# USBiso.net
KiCad netlist of a schematic drawn in Altium Designer
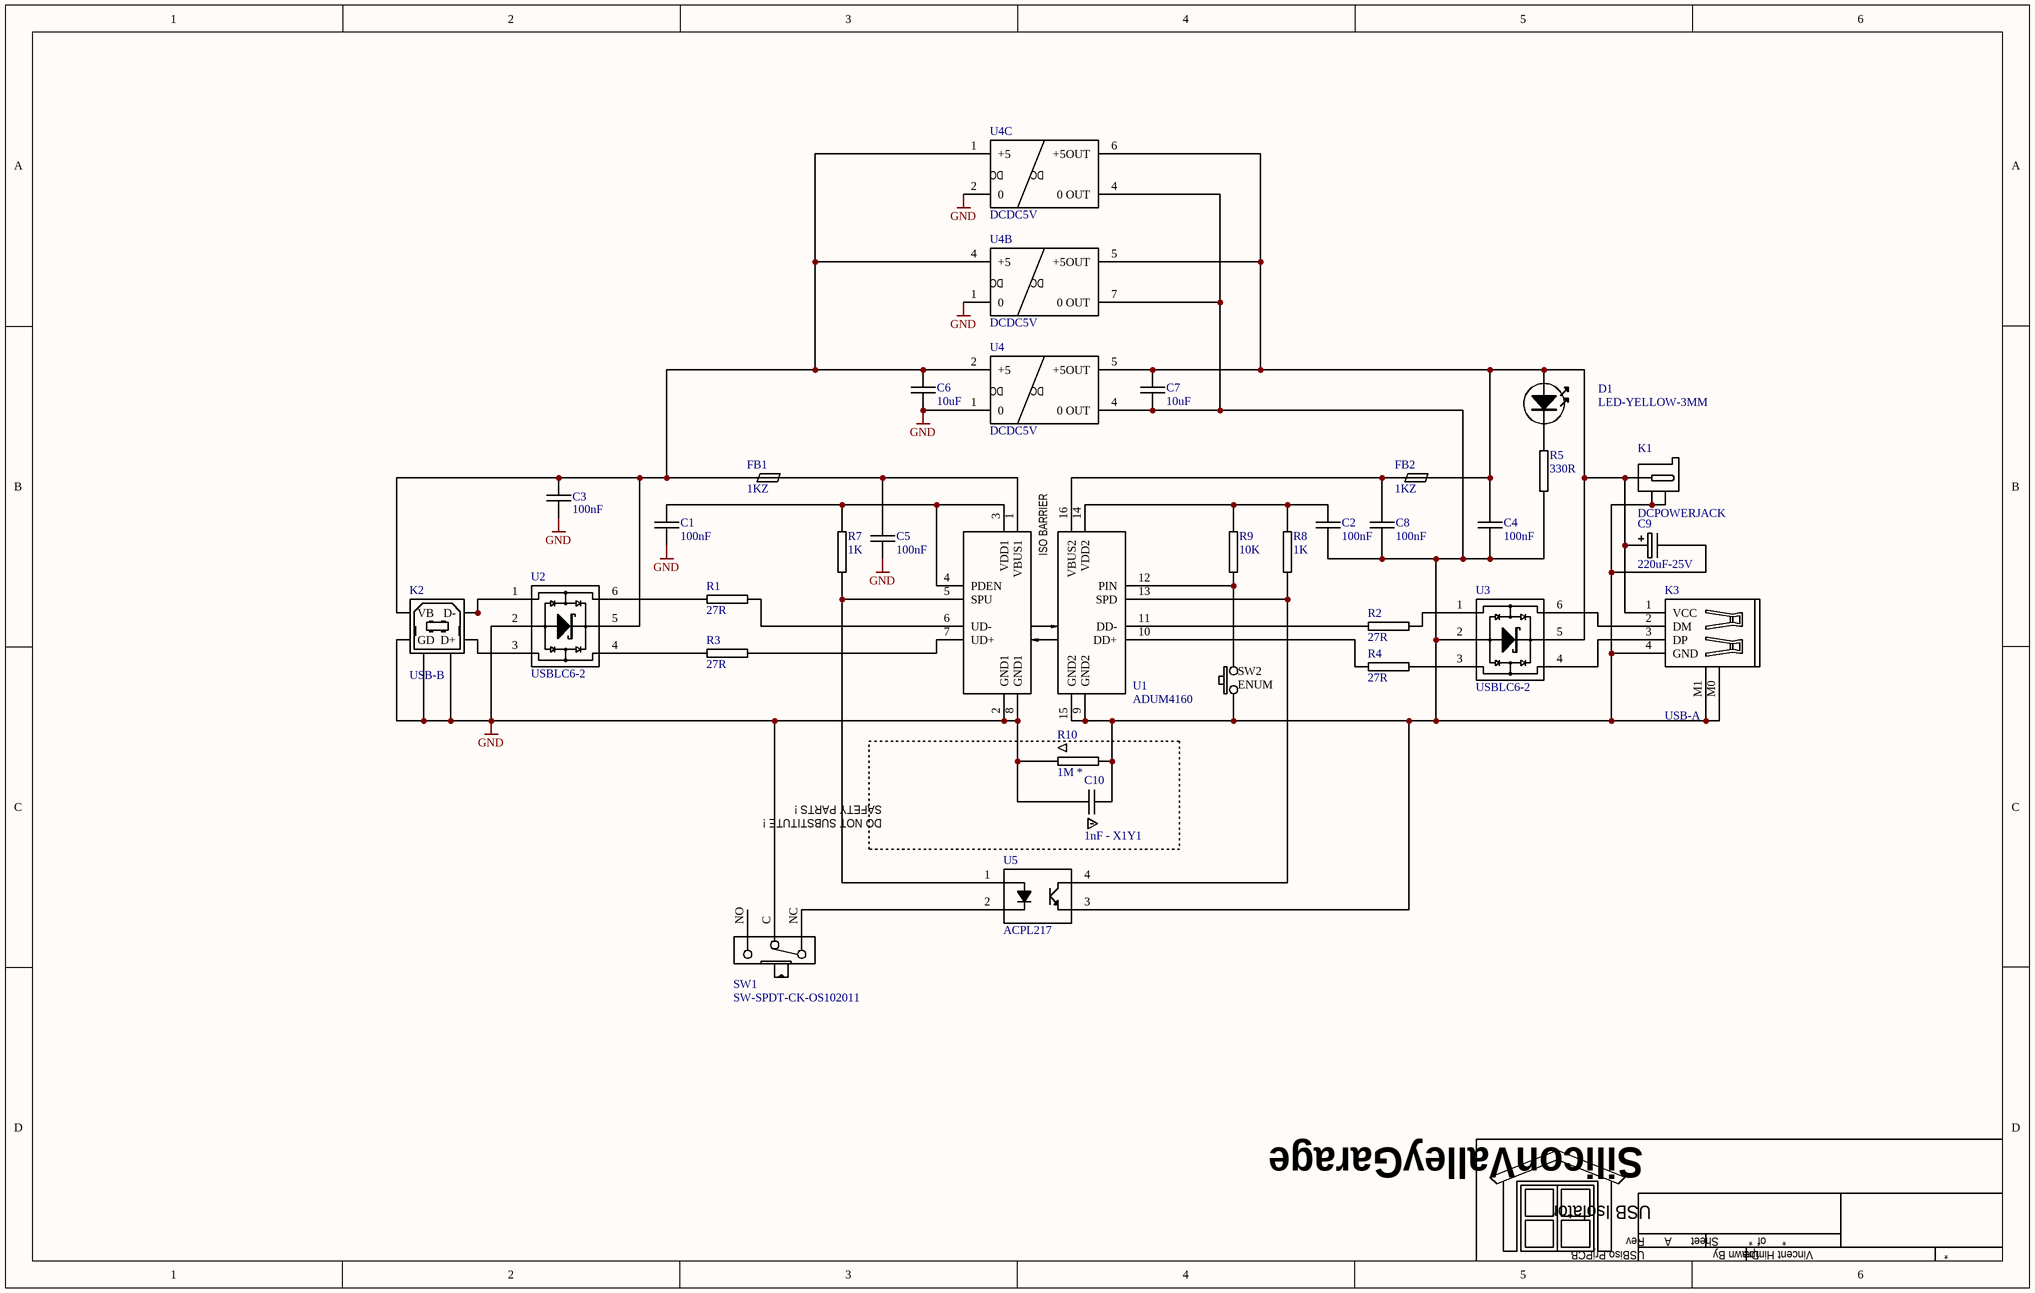
[diagram p0: USBiso.SchDoc]

(export (version "E")
  (design (tool "Eeschema 10.0.6"))
  (components
    (comp (ref "C1")
      (value "100nF")
      (footprint "0805C-TBD")
      (description "CAPACITOR 0805 CERAMIC")
      (libsource (lib "vh_Altium Library") (part "0805C-100nF-25V-X7R-MUR"))
    )
    (comp (ref "C2")
      (value "100nF")
      (footprint "0805C-TBD")
      (description "CAPACITOR 0805 CERAMIC")
      (libsource (lib "vh_Altium Library") (part "0805C-100nF-25V-X7R-MUR"))
    )
    (comp (ref "C3")
      (value "100nF")
      (footprint "0805C-TBD")
      (description "CAPACITOR 0805 CERAMIC")
      (libsource (lib "vh_Altium Library") (part "0805C-100nF-25V-X7R-MUR"))
    )
    (comp (ref "C4")
      (value "100nF")
      (footprint "0805C-TBD")
      (description "CAPACITOR 0805 CERAMIC")
      (libsource (lib "vh_Altium Library") (part "0805C-100nF-25V-X7R-MUR"))
    )
    (comp (ref "C5")
      (value "100nF")
      (footprint "0805C-TBD")
      (description "CAPACITOR 0805 CERAMIC")
      (libsource (lib "vh_Altium Library") (part "0805C-100nF-25V-X7R-MUR"))
    )
    (comp (ref "C6")
      (value "10uF")
      (footprint "0805C-GENERIC")
      (description "CAPACITOR 0805 CERAMIC")
      (fields (field (name "TOLERANCE") "±10%") (field (name "MANUFACTURER") "TDK Corporation"))
      (libsource (lib "vh_Altium Library") (part "0805C-4U7-25V-X5R-TDK"))
    )
    (comp (ref "C7")
      (value "10uF")
      (footprint "0805C-GENERIC")
      (description "CAPACITOR 0805 CERAMIC")
      (fields (field (name "TOLERANCE") "±10%") (field (name "MANUFACTURER") "TDK Corporation"))
      (libsource (lib "vh_Altium Library") (part "0805C-4U7-25V-X5R-TDK"))
    )
    (comp (ref "C8")
      (value "100nF")
      (footprint "0805C-TBD")
      (description "CAPACITOR 0805 CERAMIC")
      (libsource (lib "vh_Altium Library") (part "0805C-100nF-25V-X7R-MUR"))
    )
    (comp (ref "C9")
      (value "220uF-25V")
      (footprint "PANACAP-F-GENERIC")
      (description "GENERIC CAPACITOR POLARISED")
      (libsource (lib "SMD Capacitors Electrolytic") (part "PANACAP-220UF-25V-FK"))
    )
    (comp (ref "C10")
      (value "1nF - X1Y1")
      (footprint "C-X1Y1-10MM")
      (description "CAPACITOR X1Y1 CLASS")
      (libsource (lib "TH Capacitors") (part "C-X1Y1-10MM-1NF"))
    )
    (comp (ref "D1")
      (value "LED-YELLOW-3MM")
      (footprint "LED-3MM-YELLOW")
      (libsource (lib "vh_Altium Library") (part "LED-YELLOW-3MM"))
    )
    (comp (ref "FB1")
      (value "1KZ")
      (footprint "0805FB-1KZ")
      (description "FERRITE BEAD 1000 OHM 6A")
      (libsource (lib "SMD Magnetics") (part "0805FB-1KZ"))
    )
    (comp (ref "FB2")
      (value "1KZ")
      (footprint "0805FB-1KZ")
      (description "FERRITE BEAD 1000 OHM 6A")
      (libsource (lib "SMD Magnetics") (part "0805FB-1KZ"))
    )
    (comp (ref "K1")
      (value "DCPOWERJACK")
      (footprint "DCPOWER")
      (description "CONNN POWERJACK MINI.08\" RA PCMT")
      (fields (field (name "MANUFACTURER PART NUMBER") "RAPC722"))
      (libsource (lib "TH Connectors") (part "DCPOWERJACK"))
    )
    (comp (ref "K2")
      (value "USB-B")
      (footprint "USB-B")
      (description "USB B DEVICE CONNECTOR")
      (libsource (lib "vh_Altium Library") (part "USB-B"))
    )
    (comp (ref "K3")
      (value "USB-A")
      (footprint "usb-a")
      (description "USB A HOST CONNECTOR")
      (libsource (lib "TH Connectors") (part "USB-A"))
    )
    (comp (ref "R1")
      (value "27R")
      (footprint "0805R-27")
      (description "RESISTOR 0805 1/4 WATT THIN FILM")
      (libsource (lib "vh_Altium Library") (part "0805R-27"))
    )
    (comp (ref "R2")
      (value "27R")
      (footprint "0805R-27")
      (description "RESISTOR 0805 1/4 WATT THIN FILM")
      (libsource (lib "vh_Altium Library") (part "0805R-27"))
    )
    (comp (ref "R3")
      (value "27R")
      (footprint "0805R-27")
      (description "RESISTOR 0805 1/4 WATT THIN FILM")
      (libsource (lib "vh_Altium Library") (part "0805R-27"))
    )
    (comp (ref "R4")
      (value "27R")
      (footprint "0805R-27")
      (description "RESISTOR 0805 1/4 WATT THIN FILM")
      (libsource (lib "vh_Altium Library") (part "0805R-27"))
    )
    (comp (ref "R5")
      (value "330R")
      (footprint "0805R-330")
      (description "RESISTOR 0805 1/4 WATT THIN FILM")
      (libsource (lib "vh_Altium Library") (part "0805R-330"))
    )
    (comp (ref "R7")
      (value "1K")
      (footprint "0805R-1K")
      (description "RESISTOR 0805 1/4 WATT THIN FILM")
      (libsource (lib "vh_Altium Library") (part "0805R-1K"))
    )
    (comp (ref "R8")
      (value "1K")
      (footprint "0805R-1K")
      (description "RESISTOR 0805 1/4 WATT THIN FILM")
      (libsource (lib "vh_Altium Library") (part "0805R-1K"))
    )
    (comp (ref "R9")
      (value "10K")
      (footprint "0805R-10K")
      (description "RESISTOR 0805 1/4 WATT THIN FILM")
      (libsource (lib "vh_Altium Library") (part "0805R-10K"))
    )
    (comp (ref "R10")
      (value "1M *")
      (footprint "R-1/4W-SAFETY")
      (description "GENERIC THROUGH HOLE 1/4 WATT RESISTOR")
      (libsource (lib "TH Resistors") (part "TH4-1M-1/4W-SAFETY"))
    )
    (comp (ref "SW1")
      (value "SW-SPDT-CK-OS102011")
      (footprint "CK-OS102011")
      (description "SWITCH DPDT")
      (libsource (lib "Switches") (part "SW-SPDT-CK-OS102011"))
    )
    (comp (ref "SW2")
      (value "ENUM")
      (footprint "SW-OMRONRA-Y")
      (description "SW-D6-R / SW-DS-S / SW-14X14 / SW-7X7")
      (libsource (lib "vh_Altium Library") (part "SW-PB-YELLOW-RA"))
    )
    (comp (ref "U1")
      (value "ADUM4160")
      (footprint "SO16W")
      (description "USB Isolator")
      (libsource (lib "IC Interface") (part "ADUM4160"))
    )
    (comp (ref "U2")
      (value "USBLC6-2")
      (footprint "SOT23-6")
      (description "USB ESD PROTECTION")
      (libsource (lib "SMD Diodes") (part "USBLC6-2"))
    )
    (comp (ref "U3")
      (value "USBLC6-2")
      (footprint "SOT23-6")
      (description "USB ESD PROTECTION")
      (libsource (lib "SMD Diodes") (part "USBLC6-2"))
    )
    (comp (ref "U4")
      (value "DCDC5V")
      (footprint "VBT1-CUI")
      (description "DC DC CONVERTOR 5V - 5V SMT")
      (libsource (lib "IC Regulators") (part "VBT1-S5-S5-SMT"))
    )
    (comp (ref "U4B")
      (value "DCDC5V")
      (footprint "DCDC-DIP8")
      (description "DC DC CONVERTOR 5V - 5V")
      (libsource (lib "IC Regulators") (part "VBSD1-DIP"))
    )
    (comp (ref "U4C")
      (value "DCDC5V")
      (footprint "DCDC-SIP5")
      (description "DC DC CONVERTOR 5V - 5V")
      (libsource (lib "IC Regulators") (part "VIBLSD1-SIP"))
    )
    (comp (ref "U5")
      (value "ACPL217")
      (footprint "ACPL217")
      (description "QUAD OPTOCOUPLER")
      (libsource (lib "SMD Optoelectronics") (part "ACPL217"))
    )
  )
  (nets
    (net (code "1") (name "GND") (class "Default")
      (node (ref "C1") (pin "2") (pintype "passive"))
      (node (ref "C10") (pin "2") (pintype "passive"))
      (node (ref "C3") (pin "2") (pintype "passive"))
      (node (ref "C5") (pin "1") (pintype "passive"))
      (node (ref "C6") (pin "2") (pintype "passive"))
      (node (ref "K2") (pin "4") (pinfunction "GD_4") (pintype "passive"))
      (node (ref "K2") (pin "5") (pintype "passive"))
      (node (ref "K2") (pin "6") (pintype "passive"))
      (node (ref "R10") (pin "1") (pintype "passive"))
      (node (ref "SW1") (pin "C") (pintype "passive"))
      (node (ref "U1") (pin "2") (pinfunction "GND1_2") (pintype "passive"))
      (node (ref "U1") (pin "8") (pinfunction "GND1_8") (pintype "passive"))
      (node (ref "U2") (pin "2") (pinfunction "GND_2") (pintype "passive"))
      (node (ref "U4") (pin "1") (pinfunction "0_1") (pintype "passive"))
      (node (ref "U4B") (pin "1") (pinfunction "0_1") (pintype "passive"))
      (node (ref "U4C") (pin "2") (pinfunction "0_2") (pintype "passive"))
    )
    (net (code "2") (name "Net-(D1-PadK)") (class "Default")
      (node (ref "D1") (pin "K") (pintype "passive"))
      (node (ref "R5") (pin "2") (pintype "passive"))
    )
    (net (code "3") (name "Net-(K2-D+)") (class "Default")
      (node (ref "K2") (pin "3") (pinfunction "D+_3") (pintype "passive"))
      (node (ref "U2") (pin "3") (pinfunction "P2_3") (pintype "passive"))
    )
    (net (code "4") (name "Net-(K2-D-)") (class "Default")
      (node (ref "K2") (pin "2") (pinfunction "D-_2") (pintype "passive"))
      (node (ref "U2") (pin "1") (pinfunction "P1_1") (pintype "passive"))
    )
    (net (code "5") (name "Net-(K2-VB)") (class "Default")
      (node (ref "C3") (pin "1") (pintype "passive"))
      (node (ref "C6") (pin "1") (pintype "passive"))
      (node (ref "FB1") (pin "1") (pintype "passive"))
      (node (ref "K2") (pin "1") (pinfunction "VB_1") (pintype "passive"))
      (node (ref "U2") (pin "5") (pinfunction "VBUS_5") (pintype "passive"))
      (node (ref "U4") (pin "2") (pinfunction "+5_2") (pintype "passive"))
      (node (ref "U4B") (pin "4") (pinfunction "+5_4") (pintype "passive"))
      (node (ref "U4C") (pin "1") (pinfunction "+5_1") (pintype "passive"))
    )
    (net (code "6") (name "Net-(K3-DM)") (class "Default")
      (node (ref "K3") (pin "2") (pinfunction "DM_2") (pintype "passive"))
      (node (ref "U3") (pin "6") (pinfunction "P4_6") (pintype "passive"))
    )
    (net (code "7") (name "Net-(K3-DP)") (class "Default")
      (node (ref "K3") (pin "3") (pinfunction "DP_3") (pintype "passive"))
      (node (ref "U3") (pin "4") (pinfunction "P3_4") (pintype "passive"))
    )
    (net (code "8") (name "Net-(K3-GND)") (class "Default")
      (node (ref "C10") (pin "1") (pintype "passive"))
      (node (ref "C2") (pin "2") (pintype "passive"))
      (node (ref "C4") (pin "2") (pintype "passive"))
      (node (ref "C7") (pin "2") (pintype "passive"))
      (node (ref "C8") (pin "2") (pintype "passive"))
      (node (ref "C9") (pin "-") (pinfunction "-_-") (pintype "passive"))
      (node (ref "K1") (pin "2") (pintype "passive"))
      (node (ref "K1") (pin "3") (pintype "passive"))
      (node (ref "K3") (pin "4") (pinfunction "GND_4") (pintype "passive"))
      (node (ref "K3") (pin "M0") (pintype "passive"))
      (node (ref "K3") (pin "M1") (pintype "passive"))
      (node (ref "R10") (pin "2") (pintype "passive"))
      (node (ref "R5") (pin "1") (pintype "passive"))
      (node (ref "SW2") (pin "1") (pintype "passive"))
      (node (ref "U1") (pin "15") (pinfunction "GND2_15") (pintype "passive"))
      (node (ref "U1") (pin "9") (pinfunction "GND2_9") (pintype "passive"))
      (node (ref "U3") (pin "2") (pinfunction "GND_2") (pintype "passive"))
      (node (ref "U4") (pin "4") (pinfunction "0_OUT_4") (pintype "passive"))
      (node (ref "U4B") (pin "7") (pinfunction "0_OUT_7") (pintype "passive"))
      (node (ref "U4C") (pin "4") (pinfunction "0_OUT_4") (pintype "passive"))
      (node (ref "U5") (pin "3") (pinfunction "3_3") (pintype "passive"))
    )
    (net (code "9") (name "Net-(K3-VCC)") (class "Default")
      (node (ref "C4") (pin "1") (pintype "passive"))
      (node (ref "C7") (pin "1") (pintype "passive"))
      (node (ref "C9") (pin "+") (pinfunction "+_+") (pintype "passive"))
      (node (ref "D1") (pin "A") (pintype "passive"))
      (node (ref "FB2") (pin "2") (pintype "passive"))
      (node (ref "K1") (pin "1") (pintype "passive"))
      (node (ref "K3") (pin "1") (pinfunction "VCC_1") (pintype "passive"))
      (node (ref "U3") (pin "5") (pinfunction "VBUS_5") (pintype "passive"))
      (node (ref "U4") (pin "5") (pinfunction "+5OUT_5") (pintype "passive"))
      (node (ref "U4B") (pin "5") (pinfunction "+5OUT_5") (pintype "passive"))
      (node (ref "U4C") (pin "6") (pinfunction "+5OUT_6") (pintype "passive"))
    )
    (net (code "10") (name "Net-(SW1-NC2)") (class "Default")
      (node (ref "SW1") (pin "NC") (pinfunction "NC2_NC") (pintype "passive"))
      (node (ref "U5") (pin "2") (pinfunction "K1_2") (pintype "passive"))
    )
    (net (code "11") (name "Net-(U1-DD+)") (class "Default")
      (node (ref "R4") (pin "1") (pintype "passive"))
      (node (ref "U1") (pin "10") (pinfunction "DD+_10") (pintype "passive"))
    )
    (net (code "12") (name "Net-(U1-DD-)") (class "Default")
      (node (ref "R2") (pin "1") (pintype "passive"))
      (node (ref "U1") (pin "11") (pinfunction "DD-_11") (pintype "passive"))
    )
    (net (code "13") (name "Net-(U1-PDEN)") (class "Default")
      (node (ref "C1") (pin "1") (pintype "passive"))
      (node (ref "R7") (pin "1") (pintype "passive"))
      (node (ref "U1") (pin "3") (pinfunction "VDD1_3") (pintype "passive"))
      (node (ref "U1") (pin "4") (pinfunction "PDEN_4") (pintype "passive"))
    )
    (net (code "14") (name "Net-(U1-PIN)") (class "Default")
      (node (ref "R9") (pin "2") (pintype "passive"))
      (node (ref "SW2") (pin "2") (pintype "passive"))
      (node (ref "U1") (pin "12") (pinfunction "PIN_12") (pintype "passive"))
    )
    (net (code "15") (name "Net-(U1-SPD)") (class "Default")
      (node (ref "R8") (pin "2") (pintype "passive"))
      (node (ref "U1") (pin "13") (pinfunction "SPD_13") (pintype "passive"))
      (node (ref "U5") (pin "4") (pinfunction "4_4") (pintype "passive"))
    )
    (net (code "16") (name "Net-(U1-SPU)") (class "Default")
      (node (ref "R7") (pin "2") (pintype "passive"))
      (node (ref "U1") (pin "5") (pinfunction "SPU_5") (pintype "passive"))
      (node (ref "U5") (pin "1") (pinfunction "A1_1") (pintype "passive"))
    )
    (net (code "17") (name "Net-(U1-UD+)") (class "Default")
      (node (ref "R3") (pin "2") (pintype "passive"))
      (node (ref "U1") (pin "7") (pinfunction "UD+_7") (pintype "passive"))
    )
    (net (code "18") (name "Net-(U1-UD-)") (class "Default")
      (node (ref "R1") (pin "2") (pintype "passive"))
      (node (ref "U1") (pin "6") (pinfunction "UD-_6") (pintype "passive"))
    )
    (net (code "19") (name "Net-(U1-VBUS1)") (class "Default")
      (node (ref "C5") (pin "2") (pintype "passive"))
      (node (ref "FB1") (pin "2") (pintype "passive"))
      (node (ref "U1") (pin "1") (pinfunction "VBUS1_1") (pintype "passive"))
    )
    (net (code "20") (name "Net-(U1-VBUS2)") (class "Default")
      (node (ref "C8") (pin "1") (pintype "passive"))
      (node (ref "FB2") (pin "1") (pintype "passive"))
      (node (ref "U1") (pin "16") (pinfunction "VBUS2_16") (pintype "passive"))
    )
    (net (code "21") (name "Net-(U1-VDD2)") (class "Default")
      (node (ref "C2") (pin "1") (pintype "passive"))
      (node (ref "R8") (pin "1") (pintype "passive"))
      (node (ref "R9") (pin "1") (pintype "passive"))
      (node (ref "U1") (pin "14") (pinfunction "VDD2_14") (pintype "passive"))
    )
    (net (code "22") (name "Net-(U2-P3)") (class "Default")
      (node (ref "R3") (pin "1") (pintype "passive"))
      (node (ref "U2") (pin "4") (pinfunction "P3_4") (pintype "passive"))
    )
    (net (code "23") (name "Net-(U2-P4)") (class "Default")
      (node (ref "R1") (pin "1") (pintype "passive"))
      (node (ref "U2") (pin "6") (pinfunction "P4_6") (pintype "passive"))
    )
    (net (code "24") (name "Net-(U3-P1)") (class "Default")
      (node (ref "R2") (pin "2") (pintype "passive"))
      (node (ref "U3") (pin "1") (pinfunction "P1_1") (pintype "passive"))
    )
    (net (code "25") (name "Net-(U3-P2)") (class "Default")
      (node (ref "R4") (pin "2") (pintype "passive"))
      (node (ref "U3") (pin "3") (pinfunction "P2_3") (pintype "passive"))
    )
    (net (code "26") (name "unconnected-(SW1-PadNO)") (class "Default")
      (node (ref "SW1") (pin "NO") (pintype "passive"))
    )
  )
)
